# Serial.net
KiCad netlist of a schematic drawn in Altium Designer
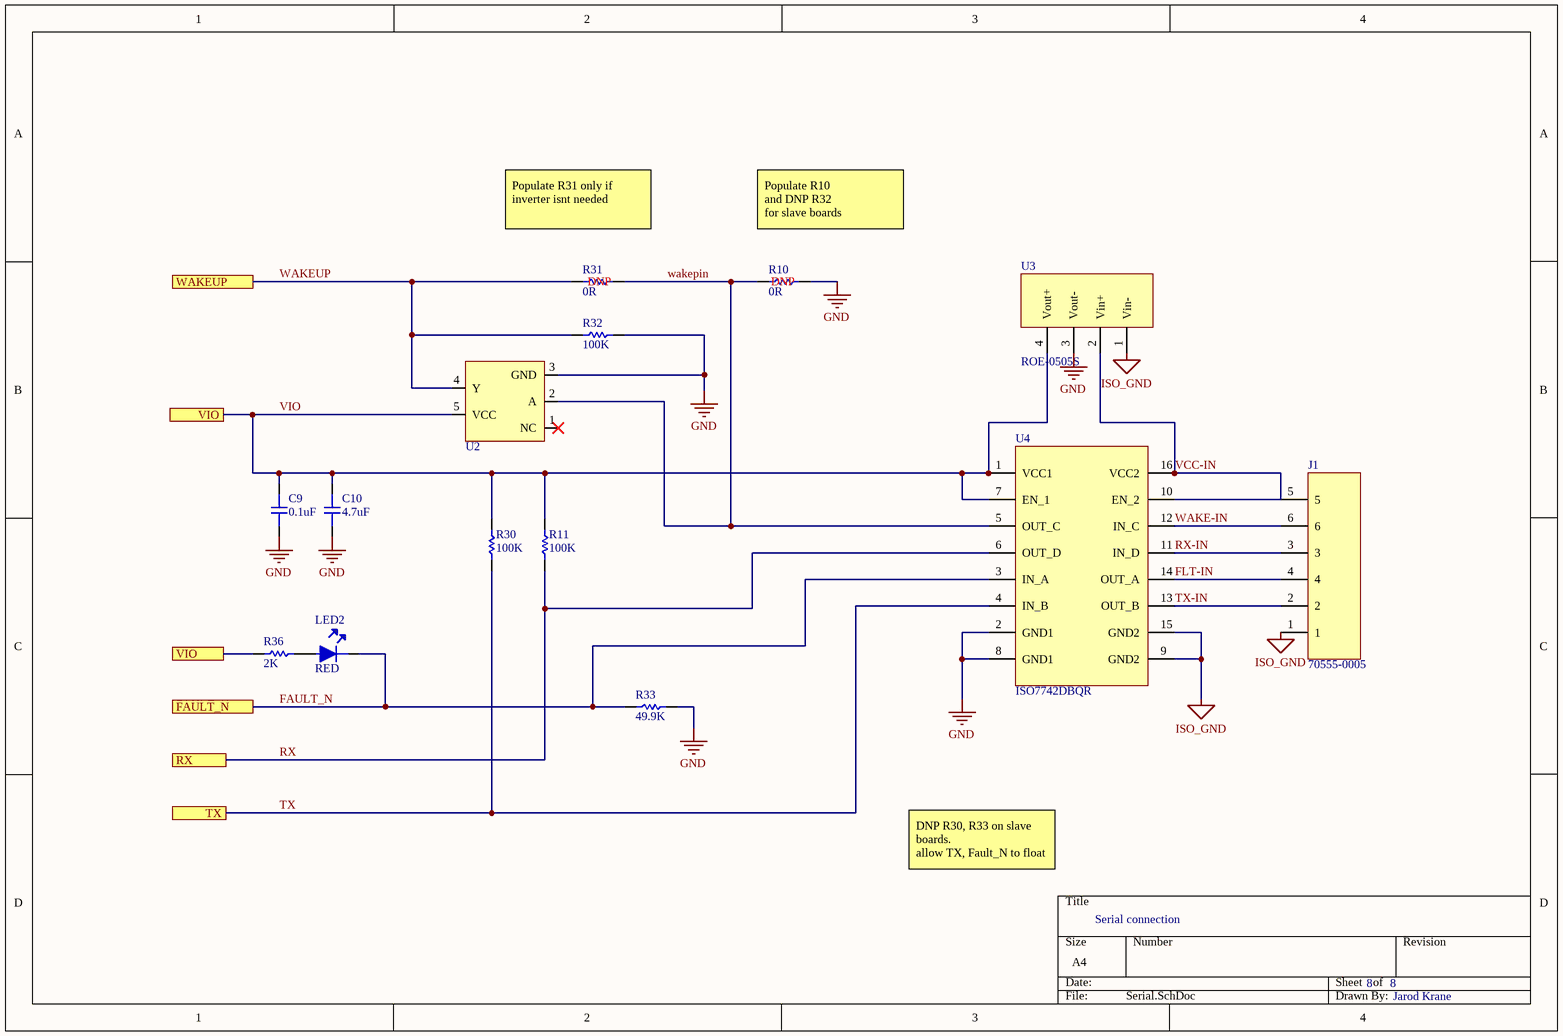
[diagram p0: Serial.SchDoc]

(export (version "E")
  (design (tool "Eeschema 10.0.6"))
  (components
    (comp (ref "C9")
      (value "0.1uF")
      (footprint "0603 CAP - duplicate")
      (description "CAP CER 0.1UF 50V X7R 0603")
      (fields
        (field (name "MANUFACTURER") "Kyocera AVX")
        (field (name "MANUFACTURER PART NUMBER") "06035C104KAZ2A")
      )
      (libsource (lib "parts") (part "06035C104KAZ2A"))
    )
    (comp (ref "C10")
      (value "4.7uF")
      (footprint "0805 CAP")
      (description "CAP CER 4.7UF 16V X7R 0805")
      (fields
        (field (name "MANUFACTURER") "Samsung")
        (field (name "MANUFACTURER PART NUMBER") "CL21B475KOFNFNE")
      )
      (libsource (lib "parts") (part "CL21B475KOFNFNE"))
    )
    (comp (ref "J1")
      (value "70555-0005")
      (footprint "SERIAL HDR")
      (description "CONN HEADER 6POS .100 R/A TIN")
      (fields (field (name "MANUFACTURER") "Molex"))
      (libsource (lib "parts") (part "70555-0005"))
    )
    (comp (ref "LED2")
      (value "RED")
      (footprint "LED2")
      (description "LED GREEN CLEAR 0603 SMD")
      (fields
        (field (name "MANUFACTURER") "Wurth Electronics")
        (field (name "MANUFACTURER PART NUMBER") "150060VS75000")
      )
      (libsource (lib "parts") (part "150060VS75000"))
    )
    (comp (ref "R10") (value "0R") (footprint "1206 RES") (libsource (lib "parts") (part "0")))
    (comp (ref "R11")
      (value "100K")
      (footprint "0603 RES")
      (description "RES SMD 100K OHM 1% 1/10W 0603")
      (fields
        (field (name "MANUFACTURER") "Panasonic")
        (field (name "MANUFACTURER PART NUMBER") "ERJ3EKF-1003V")
      )
      (libsource (lib "parts") (part "ERJ-3EKF1003V"))
    )
    (comp (ref "R30")
      (value "100K")
      (footprint "0603 RES")
      (description "RES SMD 100K OHM 1% 1/10W 0603")
      (fields
        (field (name "MANUFACTURER") "Panasonic")
        (field (name "MANUFACTURER PART NUMBER") "ERJ3EKF-1003V")
      )
      (libsource (lib "parts") (part "ERJ-3EKF1003V"))
    )
    (comp (ref "R31") (value "0R") (footprint "1206 RES") (libsource (lib "parts") (part "0")))
    (comp (ref "R32")
      (value "100K")
      (footprint "0603 RES")
      (description "RES SMD 100K OHM 1% 1/10W 0603")
      (fields
        (field (name "MANUFACTURER") "Panasonic")
        (field (name "MANUFACTURER PART NUMBER") "ERJ3EKF-1003V")
      )
      (libsource (lib "parts") (part "ERJ-3EKF1003V"))
    )
    (comp (ref "R33")
      (value "49.9K")
      (footprint "0603 RES")
      (description "RES SMD 49.9K OHM 1% 1/10W 0603")
      (libsource (lib "parts") (part "RC0603FR-0749K9L"))
    )
    (comp (ref "R36")
      (value "2K")
      (footprint "0603 RES")
      (description "RES SMD 2K OHM 1% 1/10W 0603")
      (fields
        (field (name "MANUFACTURER") "Vishay")
        (field (name "MANUFACTURER PART NUMBER") "CRCW06032K00FKEA")
      )
      (libsource (lib "parts") (part "CRCW06032K00FKEA"))
    )
    (comp (ref "U2")
      (value "NC7SZ04M5X")
      (footprint "Inverter")
      (description "IC INVERTER 1CH 1-INP SOT23-5")
      (fields (field (name "MANUFACTURER") "ON Semiconductor / Fairchild"))
      (libsource (lib "parts") (part "NC7SZ04M5X"))
    )
    (comp (ref "U3")
      (value "ROE-0505S")
      (footprint "5V-ISO")
      (description "DC DC CONVERTER 5V 1W")
      (libsource (lib "parts") (part "945-1655-5-ND"))
    )
    (comp (ref "U4")
      (value "ISO7742DBQR")
      (footprint "Serial-ISO")
      (description "DG ISO 2.5KV 4CH GEN PRP 16SSOP")
      (libsource (lib "parts") (part "296-49658-1-ND"))
    )
  )
  (nets
    (net (code "1") (name "/FAULT_N") (class "Default")
      (node (ref "LED2") (pin "2") (pinfunction "2_2") (pintype "passive"))
      (node (ref "R33") (pin "1") (pinfunction "1_1") (pintype "passive"))
      (node (ref "U4") (pin "3") (pinfunction "IN_A_3") (pintype "passive"))
    )
    (net (code "2") (name "/FLT-IN") (class "Default")
      (node (ref "J1") (pin "4") (pinfunction "4_4") (pintype "passive"))
      (node (ref "U4") (pin "14") (pinfunction "OUT_A_14") (pintype "passive"))
    )
    (net (code "3") (name "/RX") (class "Default")
      (node (ref "R11") (pin "1") (pinfunction "1_1") (pintype "passive"))
      (node (ref "U4") (pin "6") (pinfunction "OUT_D_6") (pintype "passive"))
    )
    (net (code "4") (name "/RX-IN") (class "Default")
      (node (ref "J1") (pin "3") (pinfunction "3_3") (pintype "passive"))
      (node (ref "U4") (pin "11") (pinfunction "IN_D_11") (pintype "passive"))
    )
    (net (code "5") (name "/TX") (class "Default")
      (node (ref "R30") (pin "1") (pinfunction "1_1") (pintype "passive"))
      (node (ref "U4") (pin "4") (pinfunction "IN_B_4") (pintype "passive"))
    )
    (net (code "6") (name "/TX-IN") (class "Default")
      (node (ref "J1") (pin "2") (pinfunction "2_2") (pintype "passive"))
      (node (ref "U4") (pin "13") (pinfunction "OUT_B_13") (pintype "passive"))
    )
    (net (code "7") (name "/VCC-IN") (class "Default")
      (node (ref "J1") (pin "5") (pinfunction "5_5") (pintype "passive"))
      (node (ref "U3") (pin "2") (pinfunction "Vin+_2") (pintype "passive"))
      (node (ref "U4") (pin "10") (pinfunction "EN_2_10") (pintype "passive"))
      (node (ref "U4") (pin "16") (pinfunction "VCC2_16") (pintype "passive"))
    )
    (net (code "8") (name "/VIO") (class "Default")
      (node (ref "C10") (pin "2") (pinfunction "2_2") (pintype "passive"))
      (node (ref "C9") (pin "2") (pinfunction "2_2") (pintype "passive"))
      (node (ref "R11") (pin "2") (pinfunction "2_2") (pintype "passive"))
      (node (ref "R30") (pin "2") (pinfunction "2_2") (pintype "passive"))
      (node (ref "R36") (pin "2") (pinfunction "2_2") (pintype "passive"))
      (node (ref "U2") (pin "5") (pinfunction "VCC_5") (pintype "passive"))
      (node (ref "U3") (pin "4") (pinfunction "Vout+_4") (pintype "passive"))
      (node (ref "U4") (pin "1") (pinfunction "VCC1_1") (pintype "passive"))
      (node (ref "U4") (pin "7") (pinfunction "EN_1_7") (pintype "passive"))
    )
    (net (code "9") (name "/WAKE-IN") (class "Default")
      (node (ref "J1") (pin "6") (pinfunction "6_6") (pintype "passive"))
      (node (ref "U4") (pin "12") (pinfunction "IN_C_12") (pintype "passive"))
    )
    (net (code "10") (name "/WAKEUP") (class "Default")
      (node (ref "R31") (pin "1") (pinfunction "1_1") (pintype "passive"))
      (node (ref "R32") (pin "1") (pinfunction "1_1") (pintype "passive"))
      (node (ref "U2") (pin "4") (pinfunction "Y_4") (pintype "passive"))
    )
    (net (code "11") (name "/wakepin") (class "Default")
      (node (ref "R10") (pin "1") (pinfunction "1_1") (pintype "passive"))
      (node (ref "R31") (pin "2") (pinfunction "2_2") (pintype "passive"))
      (node (ref "U2") (pin "2") (pinfunction "A_2") (pintype "passive"))
      (node (ref "U4") (pin "5") (pinfunction "OUT_C_5") (pintype "passive"))
    )
    (net (code "12") (name "GND") (class "Default")
      (node (ref "C10") (pin "1") (pinfunction "1_1") (pintype "passive"))
      (node (ref "C9") (pin "1") (pinfunction "1_1") (pintype "passive"))
      (node (ref "R10") (pin "2") (pinfunction "2_2") (pintype "passive"))
      (node (ref "R32") (pin "2") (pinfunction "2_2") (pintype "passive"))
      (node (ref "R33") (pin "2") (pinfunction "2_2") (pintype "passive"))
      (node (ref "U2") (pin "3") (pinfunction "GND_3") (pintype "passive"))
      (node (ref "U3") (pin "3") (pinfunction "Vout-_3") (pintype "passive"))
      (node (ref "U4") (pin "2") (pinfunction "GND1_2") (pintype "passive"))
      (node (ref "U4") (pin "8") (pinfunction "GND1_8") (pintype "passive"))
    )
    (net (code "13") (name "ISO_GND") (class "Default")
      (node (ref "J1") (pin "1") (pinfunction "1_1") (pintype "passive"))
      (node (ref "U3") (pin "1") (pinfunction "Vin-_1") (pintype "passive"))
      (node (ref "U4") (pin "15") (pinfunction "GND2_15") (pintype "passive"))
      (node (ref "U4") (pin "9") (pinfunction "GND2_9") (pintype "passive"))
    )
    (net (code "14") (name "Net-(LED2-Pad1)") (class "Default")
      (node (ref "LED2") (pin "1") (pinfunction "1_1") (pintype "passive"))
      (node (ref "R36") (pin "1") (pinfunction "1_1") (pintype "passive"))
    )
    (net (code "15") (name "unconnected-(U2-NC-Pad1)") (class "Default")
      (node (ref "U2") (pin "1") (pinfunction "NC_1") (pintype "passive+no_connect"))
    )
  )
)
